# layout3.net
KiCad netlist of a schematic drawn in EAGLE
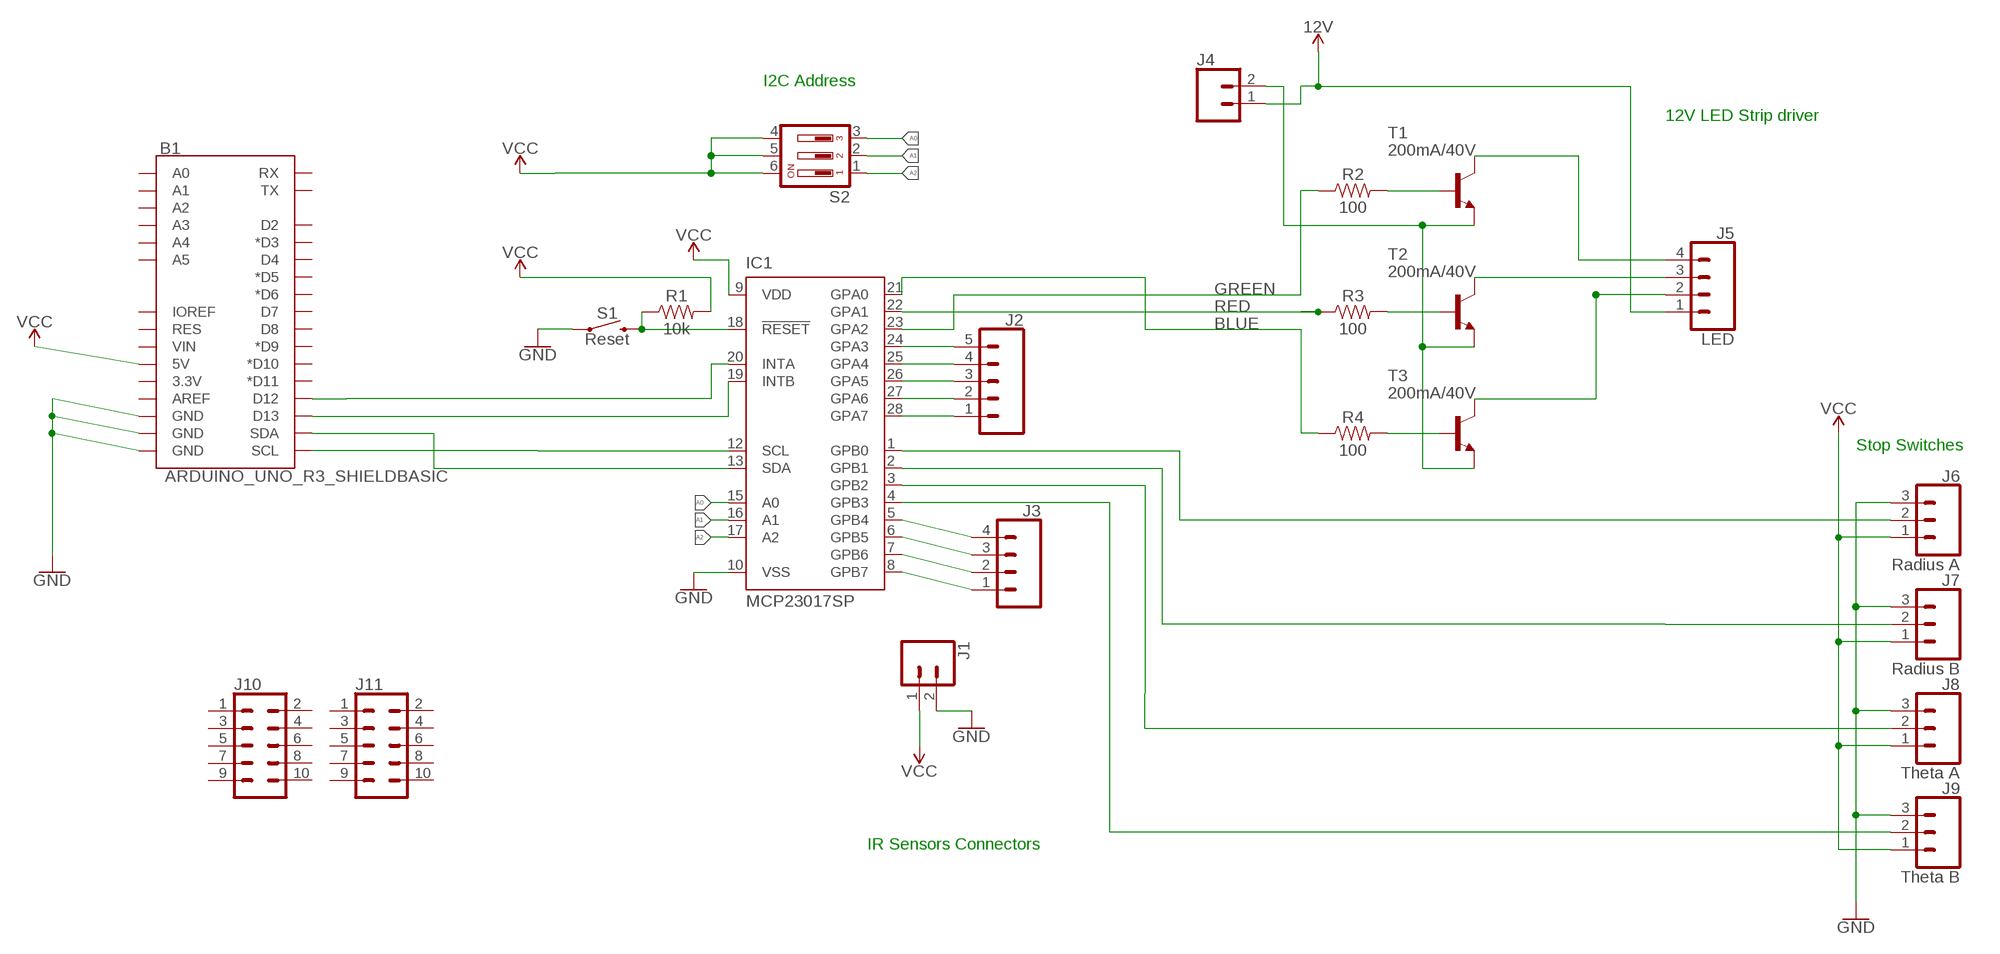
[diagram p0: schematic, sheet 1]

(export (version "E")
  (design (tool "Eeschema 10.0.6"))
  (components
    (comp (ref "B1")
      (value "ARDUINO_UNO_R3_SHIELDBASIC")
      (footprint "eagle-import:UNO_R3_SHIELD")
      (libsource (lib "eagle-import") (part "ARDUINO_UNO_R3_SHIELDBASIC"))
    )
    (comp (ref "IC1")
      (value "MCP23017SP")
      (footprint "eagle-import:DIL28-3")
      (libsource (lib "eagle-import") (part "MCP23017SP"))
    )
    (comp (ref "J1")
      (value "CONN_02POLAR")
      (footprint "eagle-import:MOLEX-1X2")
      (libsource (lib "eagle-import") (part "CONN_02POLAR"))
    )
    (comp (ref "J2")
      (value "CONN_05")
      (footprint "eagle-import:1X05")
      (libsource (lib "eagle-import") (part "CONN_05"))
    )
    (comp (ref "J3")
      (value "CONN_041.27MM")
      (footprint "eagle-import:1X04_1.27MM")
      (libsource (lib "eagle-import") (part "CONN_041.27MM"))
    )
    (comp (ref "J4")
      (value "CONN_023.5MM")
      (footprint "eagle-import:SCREWTERMINAL-3.5MM-2")
      (libsource (lib "eagle-import") (part "CONN_023.5MM"))
    )
    (comp (ref "J5")
      (value "LED")
      (footprint "eagle-import:MOLEX-1X4")
      (libsource (lib "eagle-import") (part "CONN_04POLAR"))
    )
    (comp (ref "J6")
      (value "Radius A")
      (footprint "eagle-import:MOLEX-1X3")
      (libsource (lib "eagle-import") (part "CONN_03POLAR"))
    )
    (comp (ref "J7")
      (value "Radius B")
      (footprint "eagle-import:MOLEX-1X3")
      (libsource (lib "eagle-import") (part "CONN_03POLAR"))
    )
    (comp (ref "J8")
      (value "Theta A")
      (footprint "eagle-import:MOLEX-1X3")
      (libsource (lib "eagle-import") (part "CONN_03POLAR"))
    )
    (comp (ref "J9")
      (value "Theta B")
      (footprint "eagle-import:MOLEX-1X3")
      (libsource (lib "eagle-import") (part "CONN_03POLAR"))
    )
    (comp (ref "J10")
      (value "CONN_05X2NO_SILK")
      (footprint "eagle-import:2X5_NOSILK")
      (libsource (lib "eagle-import") (part "CONN_05X2NO_SILK"))
    )
    (comp (ref "J11")
      (value "CONN_05X2NO_SILK")
      (footprint "eagle-import:2X5_NOSILK")
      (libsource (lib "eagle-import") (part "CONN_05X2NO_SILK"))
    )
    (comp (ref "R1")
      (value "10k")
      (footprint "eagle-import:0603")
      (libsource (lib "eagle-import") (part "10KOHM-0603-1/10W-1%"))
    )
    (comp (ref "R2")
      (value "100")
      (footprint "eagle-import:0603")
      (libsource (lib "eagle-import") (part "100OHM-0603-1/4W-5%"))
    )
    (comp (ref "R3")
      (value "100")
      (footprint "eagle-import:0603")
      (libsource (lib "eagle-import") (part "100OHM-0603-1/4W-5%"))
    )
    (comp (ref "R4")
      (value "100")
      (footprint "eagle-import:0603")
      (libsource (lib "eagle-import") (part "100OHM-0603-1/4W-5%"))
    )
    (comp (ref "S1")
      (value "Reset")
      (footprint "eagle-import:TACTILE_SWITCH_PTH_6.0MM")
      (libsource (lib "eagle-import") (part "MOMENTARY-SWITCH-SPST-PTH-6.0MM"))
    )
    (comp (ref "S2")
      (value "DS03")
      (footprint "eagle-import:DS-03")
      (libsource (lib "eagle-import") (part "DS03"))
    )
    (comp (ref "T1")
      (value "200mA/40V")
      (footprint "eagle-import:TO220")
      (libsource (lib "eagle-import") (part "-NPN-TO220"))
    )
    (comp (ref "T2")
      (value "200mA/40V")
      (footprint "eagle-import:TO220")
      (libsource (lib "eagle-import") (part "-NPN-TO220"))
    )
    (comp (ref "T3")
      (value "200mA/40V")
      (footprint "eagle-import:TO220")
      (libsource (lib "eagle-import") (part "-NPN-TO220"))
    )
  )
  (nets
    (net (code "1") (name "/BLUE") (class "Default")
      (node (ref "IC1") (pin "21") (pinfunction "GPA0_21") (pintype "bidirectional"))
      (node (ref "R4") (pin "1") (pinfunction "1_1") (pintype "passive"))
    )
    (net (code "2") (name "/GREEN") (class "Default")
      (node (ref "IC1") (pin "23") (pinfunction "GPA2_23") (pintype "bidirectional"))
      (node (ref "R2") (pin "1") (pinfunction "1_1") (pintype "passive"))
    )
    (net (code "3") (name "/RED") (class "Default")
      (node (ref "IC1") (pin "22") (pinfunction "GPA1_22") (pintype "bidirectional"))
      (node (ref "R3") (pin "1") (pinfunction "1_1") (pintype "passive"))
    )
    (net (code "4") (name "12V") (class "Default")
      (node (ref "J4") (pin "1") (pinfunction "1_1") (pintype "passive"))
      (node (ref "J5") (pin "1") (pinfunction "1_1") (pintype "passive"))
    )
    (net (code "5") (name "A0") (class "Default")
      (node (ref "IC1") (pin "15") (pinfunction "A0_15") (pintype "input"))
      (node (ref "S2") (pin "3") (pinfunction "3_3") (pintype "passive"))
    )
    (net (code "6") (name "A1") (class "Default")
      (node (ref "IC1") (pin "16") (pinfunction "A1_16") (pintype "input"))
      (node (ref "S2") (pin "2") (pinfunction "2_2") (pintype "passive"))
    )
    (net (code "7") (name "A2") (class "Default")
      (node (ref "IC1") (pin "17") (pinfunction "A2_17") (pintype "input"))
      (node (ref "S2") (pin "1") (pinfunction "1_1") (pintype "passive"))
    )
    (net (code "8") (name "GND") (class "Default")
      (node (ref "B1") (pin "GND@0") (pinfunction "GND_GND@0") (pintype "bidirectional"))
      (node (ref "B1") (pin "GND@1") (pinfunction "GND_GND@1") (pintype "bidirectional"))
      (node (ref "B1") (pin "GND@2") (pinfunction "GND_GND@2") (pintype "bidirectional"))
      (node (ref "IC1") (pin "10") (pinfunction "VSS_10") (pintype "power_in"))
      (node (ref "J1") (pin "2") (pinfunction "2_2") (pintype "passive"))
      (node (ref "J6") (pin "3") (pinfunction "3_3") (pintype "passive"))
      (node (ref "J7") (pin "3") (pinfunction "3_3") (pintype "passive"))
      (node (ref "J8") (pin "3") (pinfunction "3_3") (pintype "passive"))
      (node (ref "J9") (pin "3") (pinfunction "3_3") (pintype "passive"))
      (node (ref "S1") (pin "1") (pinfunction "1_1") (pintype "passive"))
    )
    (net (code "9") (name "Net-(IC1-GPA3)") (class "Default")
      (node (ref "IC1") (pin "24") (pinfunction "GPA3_24") (pintype "bidirectional"))
      (node (ref "J2") (pin "5") (pinfunction "5_5") (pintype "passive"))
    )
    (net (code "10") (name "Net-(IC1-GPA4)") (class "Default")
      (node (ref "IC1") (pin "25") (pinfunction "GPA4_25") (pintype "bidirectional"))
      (node (ref "J2") (pin "4") (pinfunction "4_4") (pintype "passive"))
    )
    (net (code "11") (name "Net-(IC1-GPA5)") (class "Default")
      (node (ref "IC1") (pin "26") (pinfunction "GPA5_26") (pintype "bidirectional"))
      (node (ref "J2") (pin "3") (pinfunction "3_3") (pintype "passive"))
    )
    (net (code "12") (name "Net-(IC1-GPA6)") (class "Default")
      (node (ref "IC1") (pin "27") (pinfunction "GPA6_27") (pintype "bidirectional"))
      (node (ref "J2") (pin "2") (pinfunction "2_2") (pintype "passive"))
    )
    (net (code "13") (name "Net-(IC1-GPA7)") (class "Default")
      (node (ref "IC1") (pin "28") (pinfunction "GPA7_28") (pintype "bidirectional"))
      (node (ref "J2") (pin "1") (pinfunction "1_1") (pintype "passive"))
    )
    (net (code "14") (name "Net-(IC1-GPB0)") (class "Default")
      (node (ref "IC1") (pin "1") (pinfunction "GPB0_1") (pintype "bidirectional"))
      (node (ref "J6") (pin "2") (pinfunction "2_2") (pintype "passive"))
    )
    (net (code "15") (name "Net-(IC1-GPB1)") (class "Default")
      (node (ref "IC1") (pin "2") (pinfunction "GPB1_2") (pintype "bidirectional"))
      (node (ref "J7") (pin "2") (pinfunction "2_2") (pintype "passive"))
    )
    (net (code "16") (name "Net-(IC1-GPB2)") (class "Default")
      (node (ref "IC1") (pin "3") (pinfunction "GPB2_3") (pintype "bidirectional"))
      (node (ref "J8") (pin "2") (pinfunction "2_2") (pintype "passive"))
    )
    (net (code "17") (name "Net-(IC1-GPB3)") (class "Default")
      (node (ref "IC1") (pin "4") (pinfunction "GPB3_4") (pintype "bidirectional"))
      (node (ref "J9") (pin "2") (pinfunction "2_2") (pintype "passive"))
    )
    (net (code "18") (name "Net-(IC1-GPB4)") (class "Default")
      (node (ref "IC1") (pin "5") (pinfunction "GPB4_5") (pintype "bidirectional"))
      (node (ref "J3") (pin "4") (pinfunction "4_4") (pintype "passive"))
    )
    (net (code "19") (name "Net-(IC1-GPB5)") (class "Default")
      (node (ref "IC1") (pin "6") (pinfunction "GPB5_6") (pintype "bidirectional"))
      (node (ref "J3") (pin "3") (pinfunction "3_3") (pintype "passive"))
    )
    (net (code "20") (name "Net-(IC1-GPB6)") (class "Default")
      (node (ref "IC1") (pin "7") (pinfunction "GPB6_7") (pintype "bidirectional"))
      (node (ref "J3") (pin "2") (pinfunction "2_2") (pintype "passive"))
    )
    (net (code "21") (name "Net-(IC1-GPB7)") (class "Default")
      (node (ref "IC1") (pin "8") (pinfunction "GPB7_8") (pintype "bidirectional"))
      (node (ref "J3") (pin "1") (pinfunction "1_1") (pintype "passive"))
    )
    (net (code "22") (name "Net-(IC1-INTA)") (class "Default")
      (node (ref "B1") (pin "D12") (pinfunction "D12_D12") (pintype "bidirectional"))
      (node (ref "IC1") (pin "20") (pinfunction "INTA_20") (pintype "output"))
    )
    (net (code "23") (name "Net-(IC1-INTB)") (class "Default")
      (node (ref "B1") (pin "D13") (pinfunction "D13_D13") (pintype "bidirectional"))
      (node (ref "IC1") (pin "19") (pinfunction "INTB_19") (pintype "output"))
    )
    (net (code "24") (name "Net-(IC1-SCL)") (class "Default")
      (node (ref "B1") (pin "SCL") (pinfunction "SCL_SCL") (pintype "bidirectional"))
      (node (ref "IC1") (pin "12") (pinfunction "SCL_12") (pintype "input"))
    )
    (net (code "25") (name "Net-(IC1-SDA)") (class "Default")
      (node (ref "B1") (pin "SDA") (pinfunction "SDA_SDA") (pintype "bidirectional"))
      (node (ref "IC1") (pin "13") (pinfunction "SDA_13") (pintype "bidirectional"))
    )
    (net (code "26") (name "Net-(IC1-~{RESET})") (class "Default")
      (node (ref "IC1") (pin "18") (pinfunction "~{RESET}_18") (pintype "input"))
      (node (ref "R1") (pin "1") (pinfunction "1_1") (pintype "passive"))
      (node (ref "S1") (pin "3") (pinfunction "2_3") (pintype "passive"))
    )
    (net (code "27") (name "Net-(T1-B)") (class "Default")
      (node (ref "R2") (pin "2") (pinfunction "2_2") (pintype "passive"))
      (node (ref "T1") (pin "1") (pinfunction "B_1") (pintype "passive"))
    )
    (net (code "28") (name "Net-(T1-C)") (class "Default")
      (node (ref "J5") (pin "4") (pinfunction "4_4") (pintype "passive"))
      (node (ref "T1") (pin "2") (pinfunction "C_2") (pintype "passive"))
    )
    (net (code "29") (name "Net-(T1-E)") (class "Default")
      (node (ref "J4") (pin "2") (pinfunction "2_2") (pintype "passive"))
      (node (ref "T1") (pin "3") (pinfunction "E_3") (pintype "passive"))
      (node (ref "T2") (pin "3") (pinfunction "E_3") (pintype "passive"))
      (node (ref "T3") (pin "3") (pinfunction "E_3") (pintype "passive"))
    )
    (net (code "30") (name "Net-(T2-B)") (class "Default")
      (node (ref "R3") (pin "2") (pinfunction "2_2") (pintype "passive"))
      (node (ref "T2") (pin "1") (pinfunction "B_1") (pintype "passive"))
    )
    (net (code "31") (name "Net-(T2-C)") (class "Default")
      (node (ref "J5") (pin "3") (pinfunction "3_3") (pintype "passive"))
      (node (ref "T2") (pin "2") (pinfunction "C_2") (pintype "passive"))
    )
    (net (code "32") (name "Net-(T3-B)") (class "Default")
      (node (ref "R4") (pin "2") (pinfunction "2_2") (pintype "passive"))
      (node (ref "T3") (pin "1") (pinfunction "B_1") (pintype "passive"))
    )
    (net (code "33") (name "Net-(T3-C)") (class "Default")
      (node (ref "J5") (pin "2") (pinfunction "2_2") (pintype "passive"))
      (node (ref "T3") (pin "2") (pinfunction "C_2") (pintype "passive"))
    )
    (net (code "34") (name "VCC") (class "Default")
      (node (ref "B1") (pin "5V") (pinfunction "5V_5V") (pintype "bidirectional"))
      (node (ref "IC1") (pin "9") (pinfunction "VDD_9") (pintype "power_in"))
      (node (ref "J1") (pin "1") (pinfunction "1_1") (pintype "passive"))
      (node (ref "J6") (pin "1") (pinfunction "1_1") (pintype "passive"))
      (node (ref "J7") (pin "1") (pinfunction "1_1") (pintype "passive"))
      (node (ref "J8") (pin "1") (pinfunction "1_1") (pintype "passive"))
      (node (ref "J9") (pin "1") (pinfunction "1_1") (pintype "passive"))
      (node (ref "R1") (pin "2") (pinfunction "2_2") (pintype "passive"))
      (node (ref "S2") (pin "4") (pinfunction "4_4") (pintype "passive"))
      (node (ref "S2") (pin "5") (pinfunction "5_5") (pintype "passive"))
      (node (ref "S2") (pin "6") (pinfunction "6_6") (pintype "passive"))
    )
    (net (code "35") (name "unconnected-(B1-*D3-PadD3)") (class "Default")
      (node (ref "B1") (pin "D3") (pinfunction "*D3_D3") (pintype "bidirectional"))
    )
    (net (code "36") (name "unconnected-(B1-*D5-PadD5)") (class "Default")
      (node (ref "B1") (pin "D5") (pinfunction "*D5_D5") (pintype "bidirectional"))
    )
    (net (code "37") (name "unconnected-(B1-*D6-PadD6)") (class "Default")
      (node (ref "B1") (pin "D6") (pinfunction "*D6_D6") (pintype "bidirectional"))
    )
    (net (code "38") (name "unconnected-(B1-*D9-PadD9)") (class "Default")
      (node (ref "B1") (pin "D9") (pinfunction "*D9_D9") (pintype "bidirectional"))
    )
    (net (code "39") (name "unconnected-(B1-*D10-PadD10)") (class "Default")
      (node (ref "B1") (pin "D10") (pinfunction "*D10_D10") (pintype "bidirectional"))
    )
    (net (code "40") (name "unconnected-(B1-*D11-PadD11)") (class "Default")
      (node (ref "B1") (pin "D11") (pinfunction "*D11_D11") (pintype "bidirectional"))
    )
    (net (code "41") (name "unconnected-(B1-Pad3.3V)") (class "Default")
      (node (ref "B1") (pin "3.3V") (pinfunction "3.3V_3.3V") (pintype "bidirectional"))
    )
    (net (code "42") (name "unconnected-(B1-PadA0)") (class "Default")
      (node (ref "B1") (pin "A0") (pinfunction "A0_A0") (pintype "bidirectional"))
    )
    (net (code "43") (name "unconnected-(B1-PadA1)") (class "Default")
      (node (ref "B1") (pin "A1") (pinfunction "A1_A1") (pintype "bidirectional"))
    )
    (net (code "44") (name "unconnected-(B1-PadA2)") (class "Default")
      (node (ref "B1") (pin "A2") (pinfunction "A2_A2") (pintype "bidirectional"))
    )
    (net (code "45") (name "unconnected-(B1-PadA3)") (class "Default")
      (node (ref "B1") (pin "A3") (pinfunction "A3_A3") (pintype "bidirectional"))
    )
    (net (code "46") (name "unconnected-(B1-PadA4)") (class "Default")
      (node (ref "B1") (pin "A4") (pinfunction "A4_A4") (pintype "bidirectional"))
    )
    (net (code "47") (name "unconnected-(B1-PadA5)") (class "Default")
      (node (ref "B1") (pin "A5") (pinfunction "A5_A5") (pintype "bidirectional"))
    )
    (net (code "48") (name "unconnected-(B1-PadAREF)") (class "Default")
      (node (ref "B1") (pin "AREF") (pinfunction "AREF_AREF") (pintype "bidirectional"))
    )
    (net (code "49") (name "unconnected-(B1-PadD2)") (class "Default")
      (node (ref "B1") (pin "D2") (pinfunction "D2_D2") (pintype "bidirectional"))
    )
    (net (code "50") (name "unconnected-(B1-PadD4)") (class "Default")
      (node (ref "B1") (pin "D4") (pinfunction "D4_D4") (pintype "bidirectional"))
    )
    (net (code "51") (name "unconnected-(B1-PadD7)") (class "Default")
      (node (ref "B1") (pin "D7") (pinfunction "D7_D7") (pintype "bidirectional"))
    )
    (net (code "52") (name "unconnected-(B1-PadD8)") (class "Default")
      (node (ref "B1") (pin "D8") (pinfunction "D8_D8") (pintype "bidirectional"))
    )
    (net (code "53") (name "unconnected-(B1-PadIOREF)") (class "Default")
      (node (ref "B1") (pin "IOREF") (pinfunction "IOREF_IOREF") (pintype "bidirectional"))
    )
    (net (code "54") (name "unconnected-(B1-PadRES)") (class "Default")
      (node (ref "B1") (pin "RES") (pinfunction "RES_RES") (pintype "bidirectional"))
    )
    (net (code "55") (name "unconnected-(B1-PadRX)") (class "Default")
      (node (ref "B1") (pin "RX") (pinfunction "RX_RX") (pintype "bidirectional"))
    )
    (net (code "56") (name "unconnected-(B1-PadTX)") (class "Default")
      (node (ref "B1") (pin "TX") (pinfunction "TX_TX") (pintype "bidirectional"))
    )
    (net (code "57") (name "unconnected-(B1-PadVIN)") (class "Default")
      (node (ref "B1") (pin "VIN") (pinfunction "VIN_VIN") (pintype "bidirectional"))
    )
    (net (code "58") (name "unconnected-(J10-Pad1)") (class "Default")
      (node (ref "J10") (pin "1") (pinfunction "1_1") (pintype "passive"))
    )
    (net (code "59") (name "unconnected-(J10-Pad2)") (class "Default")
      (node (ref "J10") (pin "2") (pinfunction "2_2") (pintype "passive"))
    )
    (net (code "60") (name "unconnected-(J10-Pad3)") (class "Default")
      (node (ref "J10") (pin "3") (pinfunction "3_3") (pintype "passive"))
    )
    (net (code "61") (name "unconnected-(J10-Pad4)") (class "Default")
      (node (ref "J10") (pin "4") (pinfunction "4_4") (pintype "passive"))
    )
    (net (code "62") (name "unconnected-(J10-Pad5)") (class "Default")
      (node (ref "J10") (pin "5") (pinfunction "5_5") (pintype "passive"))
    )
    (net (code "63") (name "unconnected-(J10-Pad6)") (class "Default")
      (node (ref "J10") (pin "6") (pinfunction "6_6") (pintype "passive"))
    )
    (net (code "64") (name "unconnected-(J10-Pad7)") (class "Default")
      (node (ref "J10") (pin "7") (pinfunction "7_7") (pintype "passive"))
    )
    (net (code "65") (name "unconnected-(J10-Pad8)") (class "Default")
      (node (ref "J10") (pin "8") (pinfunction "8_8") (pintype "passive"))
    )
    (net (code "66") (name "unconnected-(J10-Pad9)") (class "Default")
      (node (ref "J10") (pin "9") (pinfunction "9_9") (pintype "passive"))
    )
    (net (code "67") (name "unconnected-(J10-Pad10)") (class "Default")
      (node (ref "J10") (pin "10") (pinfunction "10_10") (pintype "passive"))
    )
    (net (code "68") (name "unconnected-(J11-Pad1)") (class "Default")
      (node (ref "J11") (pin "1") (pinfunction "1_1") (pintype "passive"))
    )
    (net (code "69") (name "unconnected-(J11-Pad2)") (class "Default")
      (node (ref "J11") (pin "2") (pinfunction "2_2") (pintype "passive"))
    )
    (net (code "70") (name "unconnected-(J11-Pad3)") (class "Default")
      (node (ref "J11") (pin "3") (pinfunction "3_3") (pintype "passive"))
    )
    (net (code "71") (name "unconnected-(J11-Pad4)") (class "Default")
      (node (ref "J11") (pin "4") (pinfunction "4_4") (pintype "passive"))
    )
    (net (code "72") (name "unconnected-(J11-Pad5)") (class "Default")
      (node (ref "J11") (pin "5") (pinfunction "5_5") (pintype "passive"))
    )
    (net (code "73") (name "unconnected-(J11-Pad6)") (class "Default")
      (node (ref "J11") (pin "6") (pinfunction "6_6") (pintype "passive"))
    )
    (net (code "74") (name "unconnected-(J11-Pad7)") (class "Default")
      (node (ref "J11") (pin "7") (pinfunction "7_7") (pintype "passive"))
    )
    (net (code "75") (name "unconnected-(J11-Pad8)") (class "Default")
      (node (ref "J11") (pin "8") (pinfunction "8_8") (pintype "passive"))
    )
    (net (code "76") (name "unconnected-(J11-Pad9)") (class "Default")
      (node (ref "J11") (pin "9") (pinfunction "9_9") (pintype "passive"))
    )
    (net (code "77") (name "unconnected-(J11-Pad10)") (class "Default")
      (node (ref "J11") (pin "10") (pinfunction "10_10") (pintype "passive"))
    )
  )
)
